# Schematic.net
KiCad netlist of a schematic drawn in Altium Designer
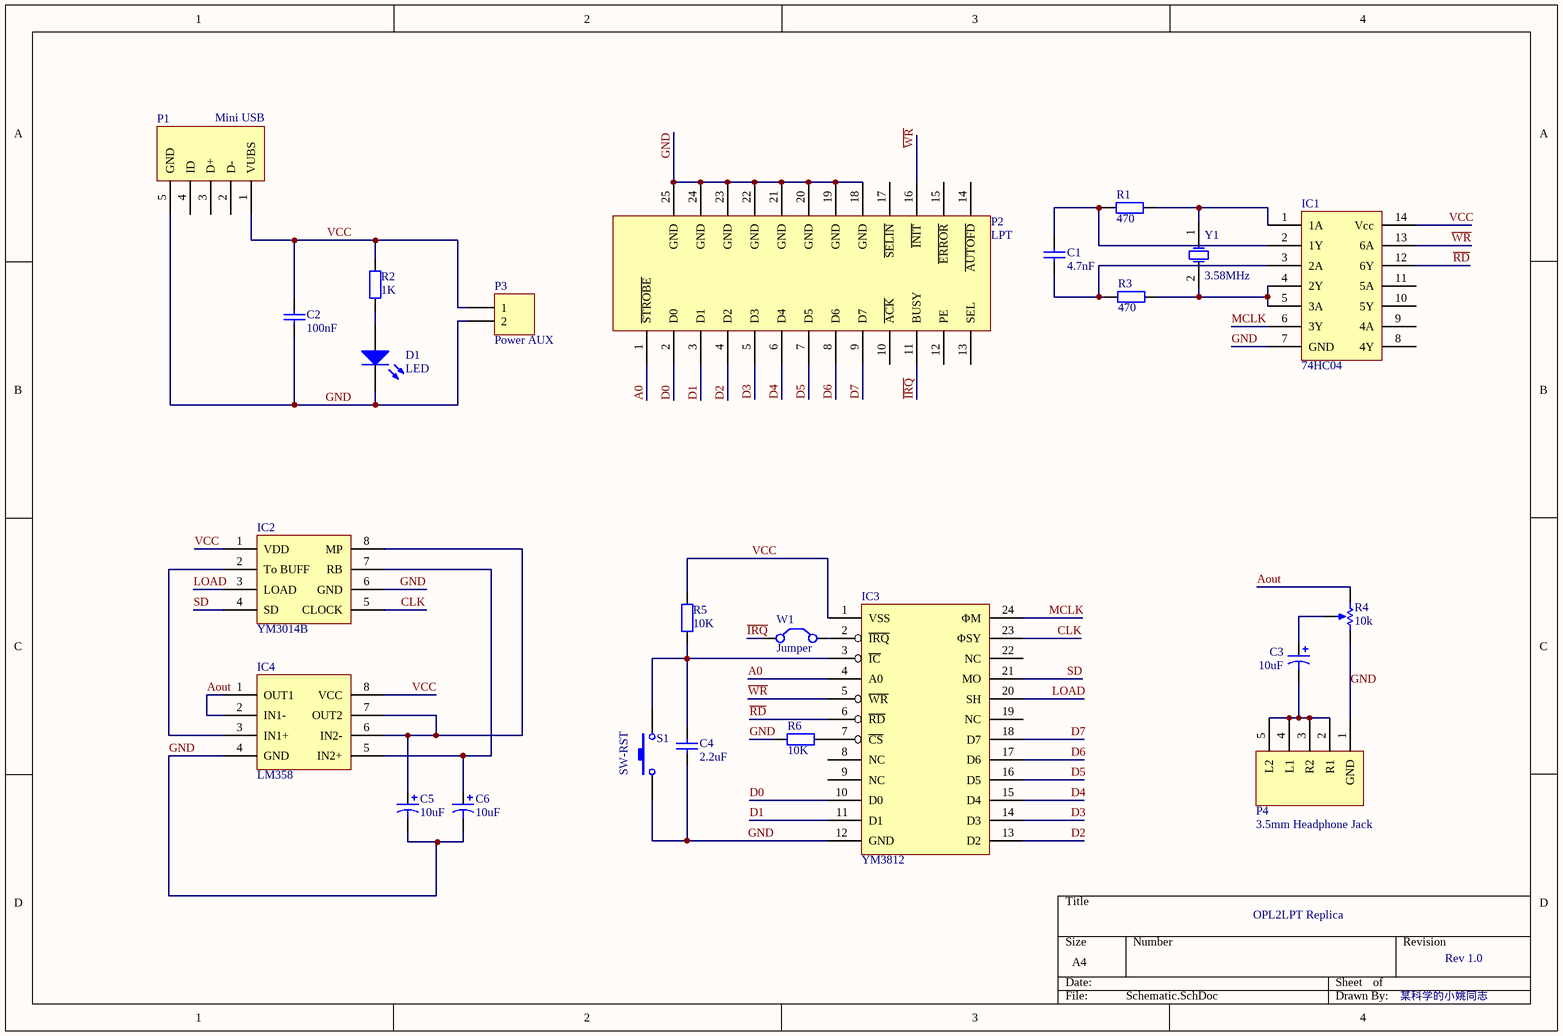
[diagram p0: Schematic.SchDoc]

(export (version "E")
  (design (tool "Eeschema 10.0.6"))
  (components
    (comp (ref "C1")
      (value "4.7nF")
      (footprint "MLCC")
      (description "Capacitor (Semiconductor SIM Model)")
      (libsource (lib "Miscellaneous Devices") (part "Cap Semi"))
    )
    (comp (ref "C2")
      (value "100nF")
      (footprint "MLCC")
      (description "Capacitor (Semiconductor SIM Model)")
      (libsource (lib "Miscellaneous Devices") (part "Cap Semi"))
    )
    (comp (ref "C3")
      (value "10uF")
      (footprint "CAP 2.0*5*11 - BK")
      (description "Polarized Capacitor (Surface Mount)")
      (libsource (lib "Miscellaneous Devices") (part "Cap Pol3"))
    )
    (comp (ref "C4")
      (value "2.2uF")
      (footprint "MLCC")
      (description "Capacitor (Semiconductor SIM Model)")
      (libsource (lib "Miscellaneous Devices") (part "Cap Semi"))
    )
    (comp (ref "C5")
      (value "10uF")
      (footprint "CAP 2.0*5*11 - BK")
      (description "Polarized Capacitor (Surface Mount)")
      (libsource (lib "Miscellaneous Devices") (part "Cap Pol3"))
    )
    (comp (ref "C6")
      (value "10uF")
      (footprint "CAP 2.0*5*11 - BK")
      (description "Polarized Capacitor (Surface Mount)")
      (libsource (lib "Miscellaneous Devices") (part "Cap Pol3"))
    )
    (comp (ref "D1")
      (value "LED")
      (footprint "LED 3MM-G")
      (description "Typical RED, GREEN, YELLOW, AMBER GaAs LED")
      (libsource (lib "Miscellaneous Devices") (part "LED2"))
    )
    (comp (ref "IC1") (value "74HC04") (footprint "DIP14-300_MH") (libsource (lib "Schlib") (part "7404")))
    (comp (ref "IC2") (value "YM3014B") (footprint "DIP8-300_MH") (libsource (lib "Schlib") (part "YM3014B")))
    (comp (ref "IC3") (value "YM3812") (footprint "DIP24-600_MH") (libsource (lib "Schlib") (part "YM3812")))
    (comp (ref "IC4") (value "LM358") (footprint "DIP8-300_MH") (libsource (lib "Schlib") (part "LM358")))
    (comp (ref "P1") (value "Mini USB") (footprint "Mini USB") (libsource (lib "Schlib") (part "Mini USB")))
    (comp (ref "P2") (value "LPT") (footprint "DB25(DR252M)") (libsource (lib "Schlib") (part "LPT")))
    (comp (ref "P3")
      (value "Power AUX")
      (footprint "HDR2.54-LI-2P")
      (description "Header, 2-Pin")
      (libsource (lib "Miscellaneous Connectors") (part "Header 2"))
    )
    (comp (ref "P4")
      (value "3.5mm Headphone Jack")
      (footprint "3F07_BK")
      (libsource (lib "Schlib") (part "3.5mm Headphone Jack"))
    )
    (comp (ref "R1")
      (value "470")
      (footprint "RS 1/4W")
      (description "Resistor")
      (libsource (lib "") (part "Res2_1"))
    )
    (comp (ref "R2")
      (value "1K")
      (footprint "RS 1/4W")
      (description "Resistor")
      (libsource (lib "Miscellaneous Devices") (part "Res2"))
    )
    (comp (ref "R3")
      (value "470")
      (footprint "RS 1/4W")
      (description "Resistor")
      (libsource (lib "") (part "Res2_1"))
    )
    (comp (ref "R4")
      (value "10k")
      (footprint "WH148-1-G15")
      (description "Potentiometer")
      (libsource (lib "Miscellaneous Devices") (part "RPot"))
    )
    (comp (ref "R5")
      (value "10K")
      (footprint "RS 1/4W")
      (description "Resistor")
      (libsource (lib "") (part "Res2_2"))
    )
    (comp (ref "R6")
      (value "10K")
      (footprint "RS 1/4W")
      (description "Resistor")
      (libsource (lib "") (part "Res2_1"))
    )
    (comp (ref "S1")
      (value "SW-RST")
      (footprint "TSW DIP-6*6*11")
      (description "Switch")
      (libsource (lib "Miscellaneous Devices") (part "SW-PB"))
    )
    (comp (ref "W1")
      (value "Jumper")
      (footprint "HDR2.54-LI-2P")
      (description "Jumper Wire")
      (libsource (lib "Miscellaneous Devices") (part "Jumper"))
    )
    (comp (ref "Y1")
      (value "3.58MHz")
      (footprint "OSC HC-49S")
      (description "Crystal Oscillator")
      (libsource (lib "Miscellaneous Devices") (part "XTAL"))
    )
  )
  (nets
    (net (code "1") (name "/A0") (class "Default")
      (node (ref "IC3") (pin "4") (pinfunction "A0_4") (pintype "passive"))
      (node (ref "P2") (pin "1") (pinfunction "~{STROBE}_1") (pintype "passive"))
    )
    (net (code "2") (name "/Aout") (class "Default")
      (node (ref "IC4") (pin "1") (pinfunction "OUT1_1") (pintype "passive"))
      (node (ref "IC4") (pin "2") (pinfunction "IN1-_2") (pintype "passive"))
      (node (ref "R4") (pin "1") (pinfunction "TOP_1") (pintype "passive"))
    )
    (net (code "3") (name "/CLK") (class "Default")
      (node (ref "IC2") (pin "5") (pinfunction "CLOCK_5") (pintype "passive"))
      (node (ref "IC3") (pin "23") (pinfunction "ΦSY_23") (pintype "passive"))
    )
    (net (code "4") (name "/D0") (class "Default")
      (node (ref "IC3") (pin "10") (pinfunction "D0_10") (pintype "passive"))
      (node (ref "P2") (pin "2") (pinfunction "D0_2") (pintype "passive"))
    )
    (net (code "5") (name "/D1") (class "Default")
      (node (ref "IC3") (pin "11") (pinfunction "D1_11") (pintype "passive"))
      (node (ref "P2") (pin "3") (pinfunction "D1_3") (pintype "passive"))
    )
    (net (code "6") (name "/D2") (class "Default")
      (node (ref "IC3") (pin "13") (pinfunction "D2_13") (pintype "passive"))
      (node (ref "P2") (pin "4") (pinfunction "D2_4") (pintype "passive"))
    )
    (net (code "7") (name "/D3") (class "Default")
      (node (ref "IC3") (pin "14") (pinfunction "D3_14") (pintype "passive"))
      (node (ref "P2") (pin "5") (pinfunction "D3_5") (pintype "passive"))
    )
    (net (code "8") (name "/D4") (class "Default")
      (node (ref "IC3") (pin "15") (pinfunction "D4_15") (pintype "passive"))
      (node (ref "P2") (pin "6") (pinfunction "D4_6") (pintype "passive"))
    )
    (net (code "9") (name "/D5") (class "Default")
      (node (ref "IC3") (pin "16") (pinfunction "D5_16") (pintype "passive"))
      (node (ref "P2") (pin "7") (pinfunction "D5_7") (pintype "passive"))
    )
    (net (code "10") (name "/D6") (class "Default")
      (node (ref "IC3") (pin "17") (pinfunction "D6_17") (pintype "passive"))
      (node (ref "P2") (pin "8") (pinfunction "D6_8") (pintype "passive"))
    )
    (net (code "11") (name "/D7") (class "Default")
      (node (ref "IC3") (pin "18") (pinfunction "D7_18") (pintype "passive"))
      (node (ref "P2") (pin "9") (pinfunction "D7_9") (pintype "passive"))
    )
    (net (code "12") (name "/GND") (class "Default")
      (node (ref "C2") (pin "1") (pinfunction "1_1") (pintype "passive"))
      (node (ref "C4") (pin "1") (pinfunction "1_1") (pintype "passive"))
      (node (ref "C5") (pin "2") (pinfunction "2_2") (pintype "passive"))
      (node (ref "C6") (pin "2") (pinfunction "2_2") (pintype "passive"))
      (node (ref "D1") (pin "2") (pinfunction "K_2") (pintype "passive"))
      (node (ref "IC1") (pin "7") (pinfunction "GND_7") (pintype "passive"))
      (node (ref "IC2") (pin "6") (pinfunction "GND_6") (pintype "passive"))
      (node (ref "IC3") (pin "12") (pinfunction "GND_12") (pintype "passive"))
      (node (ref "IC4") (pin "4") (pinfunction "GND_4") (pintype "passive"))
      (node (ref "P1") (pin "5") (pinfunction "GND_5") (pintype "passive"))
      (node (ref "P2") (pin "18") (pinfunction "GND_18") (pintype "passive"))
      (node (ref "P2") (pin "19") (pinfunction "GND_19") (pintype "passive"))
      (node (ref "P2") (pin "20") (pinfunction "GND_20") (pintype "passive"))
      (node (ref "P2") (pin "21") (pinfunction "GND_21") (pintype "passive"))
      (node (ref "P2") (pin "22") (pinfunction "GND_22") (pintype "passive"))
      (node (ref "P2") (pin "23") (pinfunction "GND_23") (pintype "passive"))
      (node (ref "P2") (pin "24") (pinfunction "GND_24") (pintype "passive"))
      (node (ref "P2") (pin "25") (pinfunction "GND_25") (pintype "passive"))
      (node (ref "P3") (pin "2") (pinfunction "2_2") (pintype "passive"))
      (node (ref "P4") (pin "1") (pinfunction "GND_1") (pintype "passive"))
      (node (ref "R4") (pin "2") (pinfunction "BOT_2") (pintype "passive"))
      (node (ref "R6") (pin "1") (pinfunction "1_1") (pintype "passive"))
      (node (ref "S1") (pin "1") (pinfunction "1_1") (pintype "passive"))
    )
    (net (code "13") (name "/LOAD") (class "Default")
      (node (ref "IC2") (pin "3") (pinfunction "LOAD_3") (pintype "passive"))
      (node (ref "IC3") (pin "20") (pinfunction "SH_20") (pintype "passive"))
    )
    (net (code "14") (name "/MCLK") (class "Default")
      (node (ref "IC1") (pin "6") (pinfunction "3Y_6") (pintype "passive"))
      (node (ref "IC3") (pin "24") (pinfunction "ΦM_24") (pintype "passive"))
    )
    (net (code "15") (name "/SD") (class "Default")
      (node (ref "IC2") (pin "4") (pinfunction "SD_4") (pintype "passive"))
      (node (ref "IC3") (pin "21") (pinfunction "MO_21") (pintype "passive"))
    )
    (net (code "16") (name "/VCC") (class "Default")
      (node (ref "C2") (pin "2") (pinfunction "2_2") (pintype "passive"))
      (node (ref "IC1") (pin "14") (pinfunction "Vcc_14") (pintype "passive"))
      (node (ref "IC2") (pin "1") (pinfunction "VDD_1") (pintype "passive"))
      (node (ref "IC3") (pin "1") (pinfunction "VSS_1") (pintype "passive"))
      (node (ref "IC4") (pin "8") (pinfunction "VCC_8") (pintype "passive"))
      (node (ref "P1") (pin "1") (pinfunction "VUBS_1") (pintype "passive"))
      (node (ref "P3") (pin "1") (pinfunction "1_1") (pintype "passive"))
      (node (ref "R2") (pin "2") (pinfunction "2_2") (pintype "passive"))
      (node (ref "R5") (pin "1") (pinfunction "1_1") (pintype "passive"))
    )
    (net (code "17") (name "/~{IRQ}") (class "Default")
      (node (ref "P2") (pin "11") (pinfunction "BUSY_11") (pintype "passive"))
      (node (ref "W1") (pin "1") (pinfunction "C1_1") (pintype "passive"))
    )
    (net (code "18") (name "/~{RD}") (class "Default")
      (node (ref "IC1") (pin "12") (pinfunction "6Y_12") (pintype "passive"))
      (node (ref "IC3") (pin "6") (pinfunction "~{RD}_6") (pintype "passive"))
    )
    (net (code "19") (name "/~{WR}") (class "Default")
      (node (ref "IC1") (pin "13") (pinfunction "6A_13") (pintype "passive"))
      (node (ref "IC3") (pin "5") (pinfunction "~{WR}_5") (pintype "passive"))
      (node (ref "P2") (pin "16") (pinfunction "~{INIT}_16") (pintype "passive"))
    )
    (net (code "20") (name "Net-(D1-A)") (class "Default")
      (node (ref "D1") (pin "1") (pinfunction "A_1") (pintype "passive"))
      (node (ref "R2") (pin "1") (pinfunction "1_1") (pintype "passive"))
    )
    (net (code "21") (name "Net-(IC1-1A)") (class "Default")
      (node (ref "IC1") (pin "1") (pinfunction "1A_1") (pintype "passive"))
      (node (ref "R1") (pin "2") (pinfunction "2_2") (pintype "passive"))
      (node (ref "Y1") (pin "1") (pinfunction "OSC1_1") (pintype "passive"))
    )
    (net (code "22") (name "Net-(IC1-1Y)") (class "Default")
      (node (ref "C1") (pin "2") (pinfunction "2_2") (pintype "passive"))
      (node (ref "IC1") (pin "2") (pinfunction "1Y_2") (pintype "passive"))
      (node (ref "R1") (pin "1") (pinfunction "1_1") (pintype "passive"))
    )
    (net (code "23") (name "Net-(IC1-2A)") (class "Default")
      (node (ref "C1") (pin "1") (pinfunction "1_1") (pintype "passive"))
      (node (ref "IC1") (pin "3") (pinfunction "2A_3") (pintype "passive"))
      (node (ref "R3") (pin "1") (pinfunction "1_1") (pintype "passive"))
    )
    (net (code "24") (name "Net-(IC1-2Y)") (class "Default")
      (node (ref "IC1") (pin "4") (pinfunction "2Y_4") (pintype "passive"))
      (node (ref "IC1") (pin "5") (pinfunction "3A_5") (pintype "passive"))
      (node (ref "R3") (pin "2") (pinfunction "2_2") (pintype "passive"))
      (node (ref "Y1") (pin "2") (pinfunction "OSC2_2") (pintype "passive"))
    )
    (net (code "25") (name "Net-(IC2-MP)") (class "Default")
      (node (ref "C5") (pin "1") (pinfunction "1_1") (pintype "passive"))
      (node (ref "IC2") (pin "8") (pinfunction "MP_8") (pintype "passive"))
      (node (ref "IC4") (pin "6") (pinfunction "IN2-_6") (pintype "passive"))
      (node (ref "IC4") (pin "7") (pinfunction "OUT2_7") (pintype "passive"))
    )
    (net (code "26") (name "Net-(IC2-RB)") (class "Default")
      (node (ref "C6") (pin "1") (pinfunction "1_1") (pintype "passive"))
      (node (ref "IC2") (pin "7") (pinfunction "RB_7") (pintype "passive"))
      (node (ref "IC4") (pin "5") (pinfunction "IN2+_5") (pintype "passive"))
    )
    (net (code "27") (name "Net-(IC2-To_BUFF)") (class "Default")
      (node (ref "IC2") (pin "2") (pinfunction "To_BUFF_2") (pintype "passive"))
      (node (ref "IC4") (pin "3") (pinfunction "IN1+_3") (pintype "passive"))
    )
    (net (code "28") (name "Net-(IC3-~{CS})") (class "Default")
      (node (ref "IC3") (pin "7") (pinfunction "~{CS}_7") (pintype "passive"))
      (node (ref "R6") (pin "2") (pinfunction "2_2") (pintype "passive"))
    )
    (net (code "29") (name "Net-(IC3-~{IC})") (class "Default")
      (node (ref "C4") (pin "2") (pinfunction "2_2") (pintype "passive"))
      (node (ref "IC3") (pin "3") (pinfunction "~{IC}_3") (pintype "passive"))
      (node (ref "R5") (pin "2") (pinfunction "2_2") (pintype "passive"))
      (node (ref "S1") (pin "2") (pinfunction "2_2") (pintype "passive"))
    )
    (net (code "30") (name "Net-(IC3-~{IRQ})") (class "Default")
      (node (ref "IC3") (pin "2") (pinfunction "~{IRQ}_2") (pintype "passive"))
      (node (ref "W1") (pin "2") (pinfunction "C2_2") (pintype "passive"))
    )
    (net (code "31") (name "Net-(P4-L1)") (class "Default")
      (node (ref "C3") (pin "2") (pinfunction "2_2") (pintype "passive"))
      (node (ref "P4") (pin "2") (pinfunction "R1_2") (pintype "passive"))
      (node (ref "P4") (pin "3") (pinfunction "R2_3") (pintype "passive"))
      (node (ref "P4") (pin "4") (pinfunction "L1_4") (pintype "passive"))
      (node (ref "P4") (pin "5") (pinfunction "L2_5") (pintype "passive"))
    )
    (net (code "32") (name "Net-(R4-TAP)") (class "Default")
      (node (ref "C3") (pin "1") (pinfunction "1_1") (pintype "passive"))
      (node (ref "R4") (pin "3") (pinfunction "TAP_3") (pintype "passive"))
    )
    (net (code "33") (name "unconnected-(IC1-4A-Pad9)") (class "Default")
      (node (ref "IC1") (pin "9") (pinfunction "4A_9") (pintype "passive"))
    )
    (net (code "34") (name "unconnected-(IC1-4Y-Pad8)") (class "Default")
      (node (ref "IC1") (pin "8") (pinfunction "4Y_8") (pintype "passive"))
    )
    (net (code "35") (name "unconnected-(IC1-5A-Pad11)") (class "Default")
      (node (ref "IC1") (pin "11") (pinfunction "5A_11") (pintype "passive"))
    )
    (net (code "36") (name "unconnected-(IC1-5Y-Pad10)") (class "Default")
      (node (ref "IC1") (pin "10") (pinfunction "5Y_10") (pintype "passive"))
    )
    (net (code "37") (name "unconnected-(IC3-NC-Pad8)") (class "Default")
      (node (ref "IC3") (pin "8") (pinfunction "NC_8") (pintype "passive"))
    )
    (net (code "38") (name "unconnected-(IC3-NC-Pad9)") (class "Default")
      (node (ref "IC3") (pin "9") (pinfunction "NC_9") (pintype "passive"))
    )
    (net (code "39") (name "unconnected-(IC3-NC-Pad19)") (class "Default")
      (node (ref "IC3") (pin "19") (pinfunction "NC_19") (pintype "passive"))
    )
    (net (code "40") (name "unconnected-(IC3-NC-Pad22)") (class "Default")
      (node (ref "IC3") (pin "22") (pinfunction "NC_22") (pintype "passive"))
    )
    (net (code "41") (name "unconnected-(P1-D+-Pad3)") (class "Default")
      (node (ref "P1") (pin "3") (pinfunction "D+_3") (pintype "passive"))
    )
    (net (code "42") (name "unconnected-(P1-D--Pad2)") (class "Default")
      (node (ref "P1") (pin "2") (pinfunction "D-_2") (pintype "passive"))
    )
    (net (code "43") (name "unconnected-(P1-ID-Pad4)") (class "Default")
      (node (ref "P1") (pin "4") (pinfunction "ID_4") (pintype "passive"))
    )
    (net (code "44") (name "unconnected-(P2-PE-Pad12)") (class "Default")
      (node (ref "P2") (pin "12") (pinfunction "PE_12") (pintype "passive"))
    )
    (net (code "45") (name "unconnected-(P2-SEL-Pad13)") (class "Default")
      (node (ref "P2") (pin "13") (pinfunction "SEL_13") (pintype "passive"))
    )
    (net (code "46") (name "unconnected-(P2-~{ACK}-Pad10)") (class "Default")
      (node (ref "P2") (pin "10") (pinfunction "~{ACK}_10") (pintype "passive"))
    )
    (net (code "47") (name "unconnected-(P2-~{AUTOFD}-Pad14)") (class "Default")
      (node (ref "P2") (pin "14") (pinfunction "~{AUTOFD}_14") (pintype "passive"))
    )
    (net (code "48") (name "unconnected-(P2-~{ERROR}-Pad15)") (class "Default")
      (node (ref "P2") (pin "15") (pinfunction "~{ERROR}_15") (pintype "passive"))
    )
    (net (code "49") (name "unconnected-(P2-~{SELIN}-Pad17)") (class "Default")
      (node (ref "P2") (pin "17") (pinfunction "~{SELIN}_17") (pintype "passive"))
    )
  )
)
